# AD7298_12-Bit_SPI_ADC.net
KiCad netlist of a schematic drawn in Altium Designer
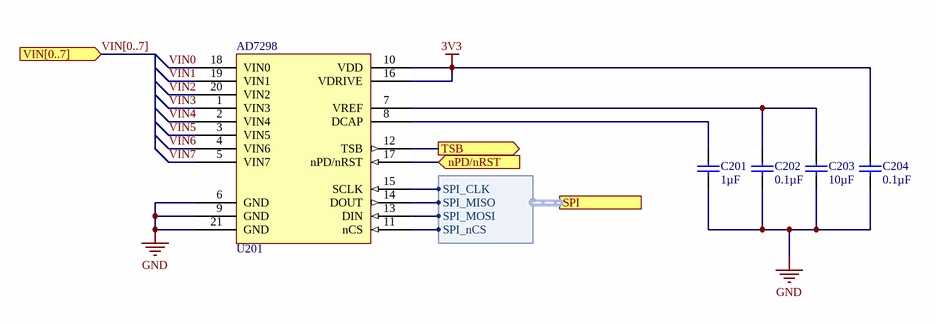
[diagram p0: AD7298 12-Bit SPI ADC.SchDoc]

(export (version "E")
  (design (tool "Eeschema 10.0.6"))
  (components
    (comp (ref "C201")
      (value "1µF")
      (footprint "TDK-CGA3E")
      (description "CAP CER 1UF 25V X7R 0603")
      (fields
        (field (name "PART NUMBER") "PC-TDK-02603")
        (field (name "MANUFACTURER PART NUMBER") "CGA3E1X7R1E105K080AC")
        (field (name "PUBLISHER") "AlbertaSat")
      )
      (libsource (lib "Database") (part "Cap"))
    )
    (comp (ref "C202")
      (value "0.1µF")
      (footprint "TDK-CGA2B")
      (description "CAP CER 0.1UF 50V X7R 0402")
      (fields
        (field (name "PART NUMBER") "PC-TDK-02259")
        (field (name "MANUFACTURER PART NUMBER") "CGA2B3X7R1H104K050BB")
        (field (name "PUBLISHER") "AlbertaSat")
      )
      (libsource (lib "Database") (part "Cap"))
    )
    (comp (ref "C203")
      (value "10µF")
      (footprint "TDK-CGA5L")
      (description "CAP CER 10UF 25V X7R 1206")
      (fields
        (field (name "PART NUMBER") "PC-TDK-02917")
        (field (name "MANUFACTURER PART NUMBER") "CGA5L1X7R1E106K160AC")
        (field (name "PUBLISHER") "AlbertaSat")
      )
      (libsource (lib "Database") (part "Cap"))
    )
    (comp (ref "C204")
      (value "0.1µF")
      (footprint "TDK-CGA2B")
      (description "CAP CER 0.1UF 50V X7R 0402")
      (fields
        (field (name "PART NUMBER") "PC-TDK-02259")
        (field (name "MANUFACTURER PART NUMBER") "CGA2B3X7R1H104K050BB")
        (field (name "PUBLISHER") "AlbertaSat")
      )
      (libsource (lib "Database") (part "Cap"))
    )
    (comp (ref "U201")
      (value "AD7298")
      (footprint "ADI-CP-20-8")
      (description "IC ADC 12BIT SAR 20LFCSP-WQ")
      (fields
        (field (name "PART NUMBER") "PU-ADI-00007")
        (field (name "MANUFACTURER PART NUMBER") "AD7298BCPZ")
        (field (name "PUBLISHER") "AlbertaSat")
      )
      (libsource (lib "Database") (part "AD7298"))
    )
  )
  (nets
    (net (code "2") (name "/SPI_CLK") (class "Default")
      (node (ref "U201") (pin "15") (pinfunction "SCLK_15") (pintype "input"))
    )
    (net (code "3") (name "/SPI_MISO") (class "Default")
      (node (ref "U201") (pin "14") (pinfunction "DOUT_14") (pintype "output"))
    )
    (net (code "4") (name "/SPI_MOSI") (class "Default")
      (node (ref "U201") (pin "13") (pinfunction "DIN_13") (pintype "input"))
    )
    (net (code "5") (name "/SPI_nCS") (class "Default")
      (node (ref "U201") (pin "11") (pinfunction "nCS_11") (pintype "input"))
    )
    (net (code "6") (name "/TSB") (class "Default")
      (node (ref "U201") (pin "12") (pinfunction "TSB_12") (pintype "output"))
    )
    (net (code "7") (name "/VIN0") (class "Default")
      (node (ref "U201") (pin "18") (pinfunction "VIN0_18") (pintype "passive"))
    )
    (net (code "8") (name "/VIN1") (class "Default")
      (node (ref "U201") (pin "19") (pinfunction "VIN1_19") (pintype "passive"))
    )
    (net (code "9") (name "/VIN2") (class "Default")
      (node (ref "U201") (pin "20") (pinfunction "VIN2_20") (pintype "passive"))
    )
    (net (code "10") (name "/VIN3") (class "Default")
      (node (ref "U201") (pin "1") (pinfunction "VIN3_1") (pintype "passive"))
    )
    (net (code "11") (name "/VIN4") (class "Default")
      (node (ref "U201") (pin "2") (pinfunction "VIN4_2") (pintype "passive"))
    )
    (net (code "12") (name "/VIN5") (class "Default")
      (node (ref "U201") (pin "3") (pinfunction "VIN5_3") (pintype "passive"))
    )
    (net (code "13") (name "/VIN6") (class "Default")
      (node (ref "U201") (pin "4") (pinfunction "VIN6_4") (pintype "passive"))
    )
    (net (code "14") (name "/VIN7") (class "Default")
      (node (ref "U201") (pin "5") (pinfunction "VIN7_5") (pintype "passive"))
    )
    (net (code "16") (name "/nPD{slash}nRST") (class "Default")
      (node (ref "U201") (pin "17") (pinfunction "nPD/nRST_17") (pintype "input"))
    )
    (net (code "18") (name "3V3") (class "Default")
      (node (ref "C204") (pin "1") (pinfunction "1_1") (pintype "passive"))
      (node (ref "U201") (pin "10") (pinfunction "VDD_10") (pintype "passive"))
      (node (ref "U201") (pin "16") (pinfunction "VDRIVE_16") (pintype "passive"))
    )
    (net (code "19") (name "GND") (class "Default")
      (node (ref "C201") (pin "1") (pinfunction "1_1") (pintype "passive"))
      (node (ref "C202") (pin "2") (pinfunction "2_2") (pintype "passive"))
      (node (ref "C203") (pin "2") (pinfunction "2_2") (pintype "passive"))
      (node (ref "C204") (pin "2") (pinfunction "2_2") (pintype "passive"))
      (node (ref "U201") (pin "21") (pinfunction "GND_21") (pintype "passive"))
      (node (ref "U201") (pin "6") (pinfunction "GND_6") (pintype "passive"))
      (node (ref "U201") (pin "9") (pinfunction "GND_9") (pintype "passive"))
    )
    (net (code "20") (name "Net-(U201-DCAP)") (class "Default")
      (node (ref "C201") (pin "2") (pinfunction "2_2") (pintype "passive"))
      (node (ref "U201") (pin "8") (pinfunction "DCAP_8") (pintype "passive"))
    )
    (net (code "21") (name "Net-(U201-VREF)") (class "Default")
      (node (ref "C202") (pin "1") (pinfunction "1_1") (pintype "passive"))
      (node (ref "C203") (pin "1") (pinfunction "1_1") (pintype "passive"))
      (node (ref "U201") (pin "7") (pinfunction "VREF_7") (pintype "passive"))
    )
  )
)
